# PIC32ETH_Pic.net
KiCad netlist of a schematic drawn in Altium Designer
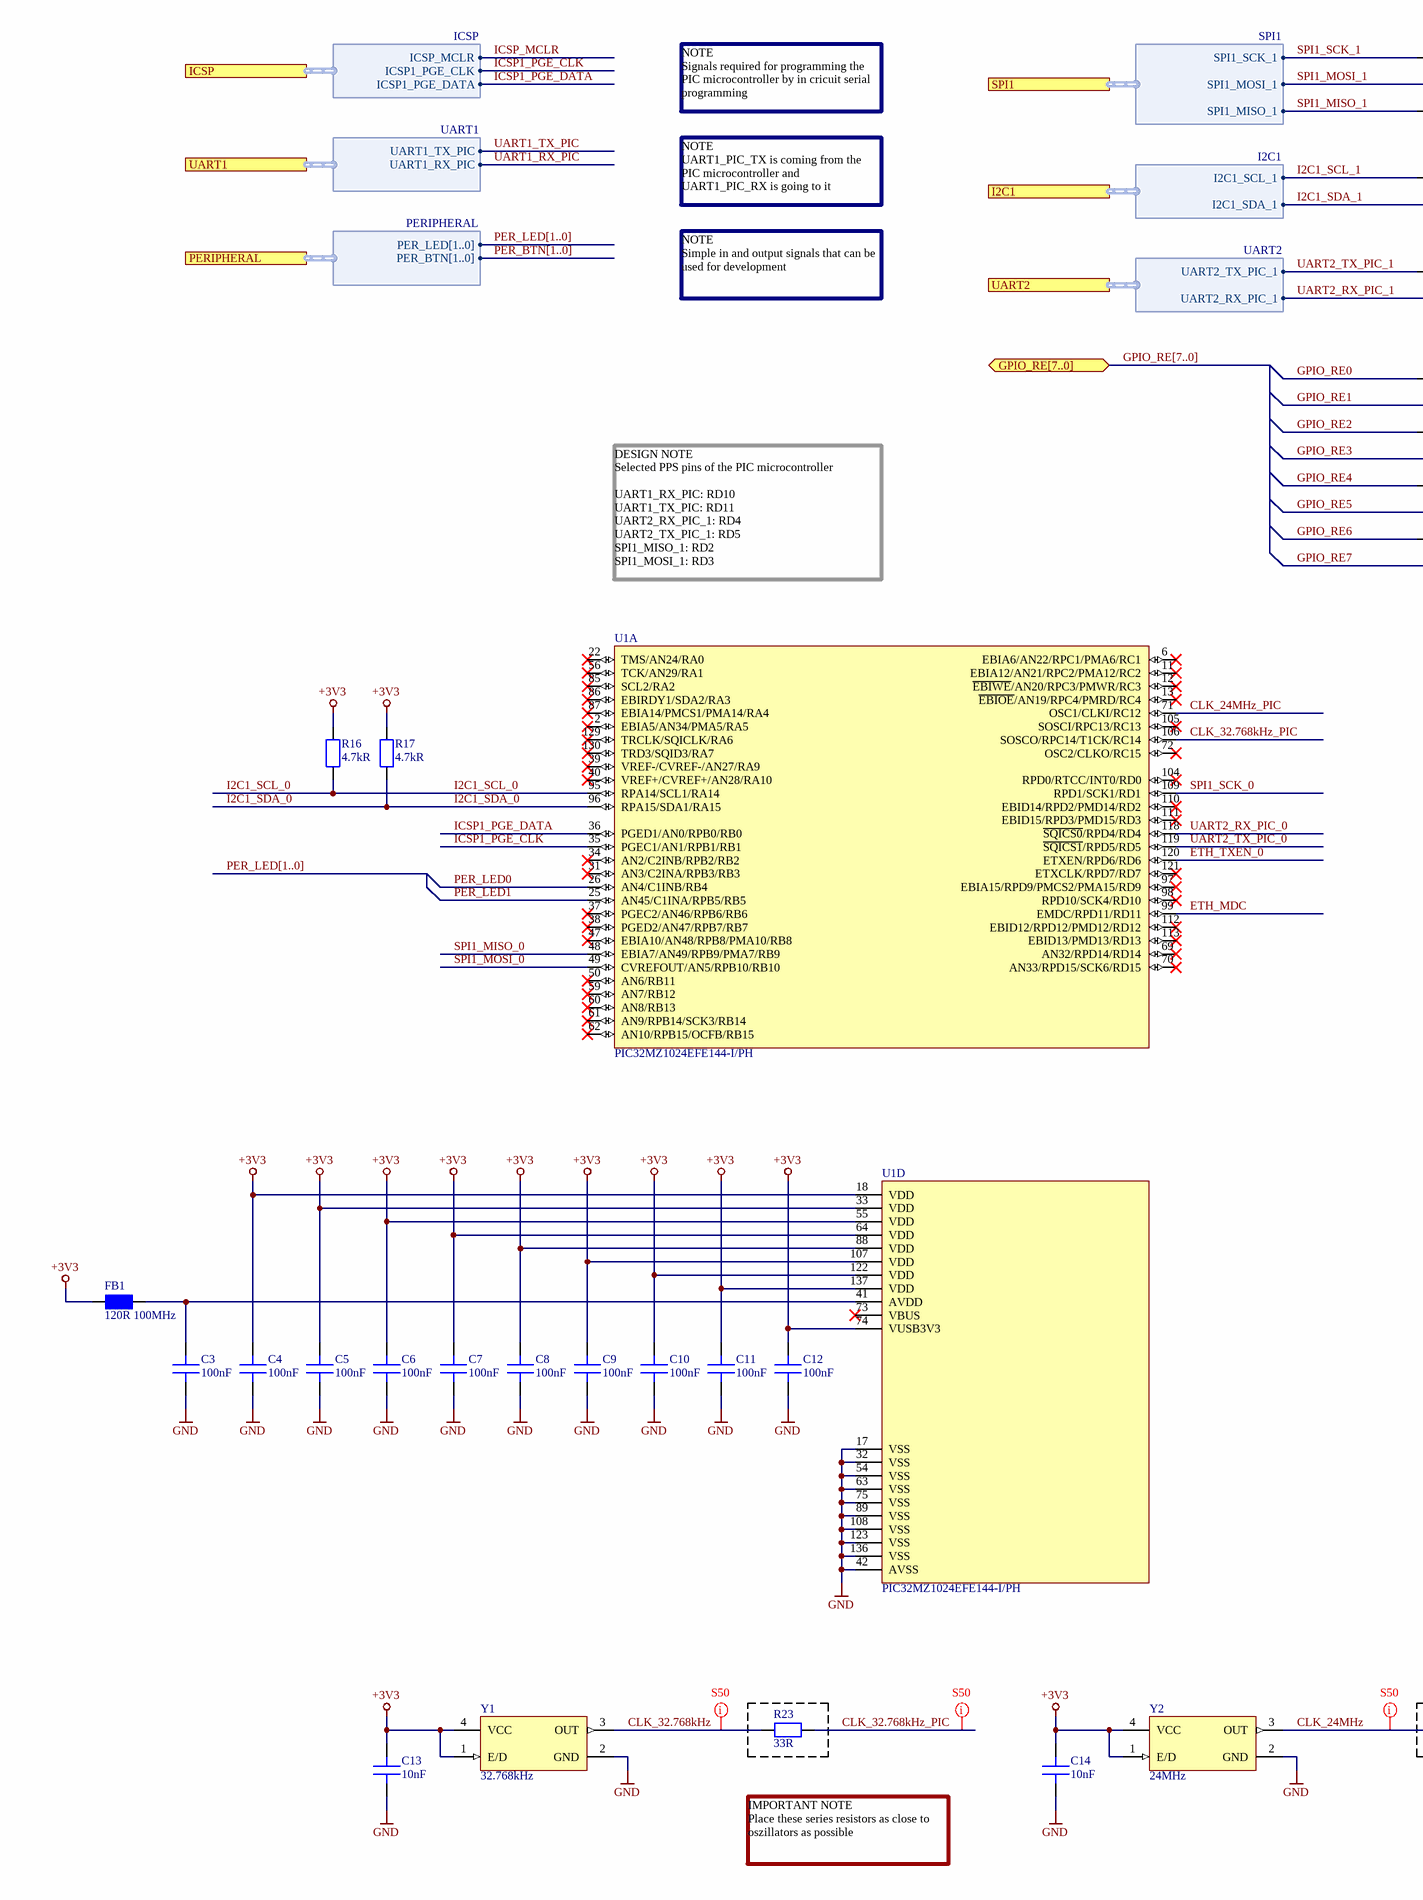
[diagram p0: PIC32ETH_Pic.SchDoc, left]
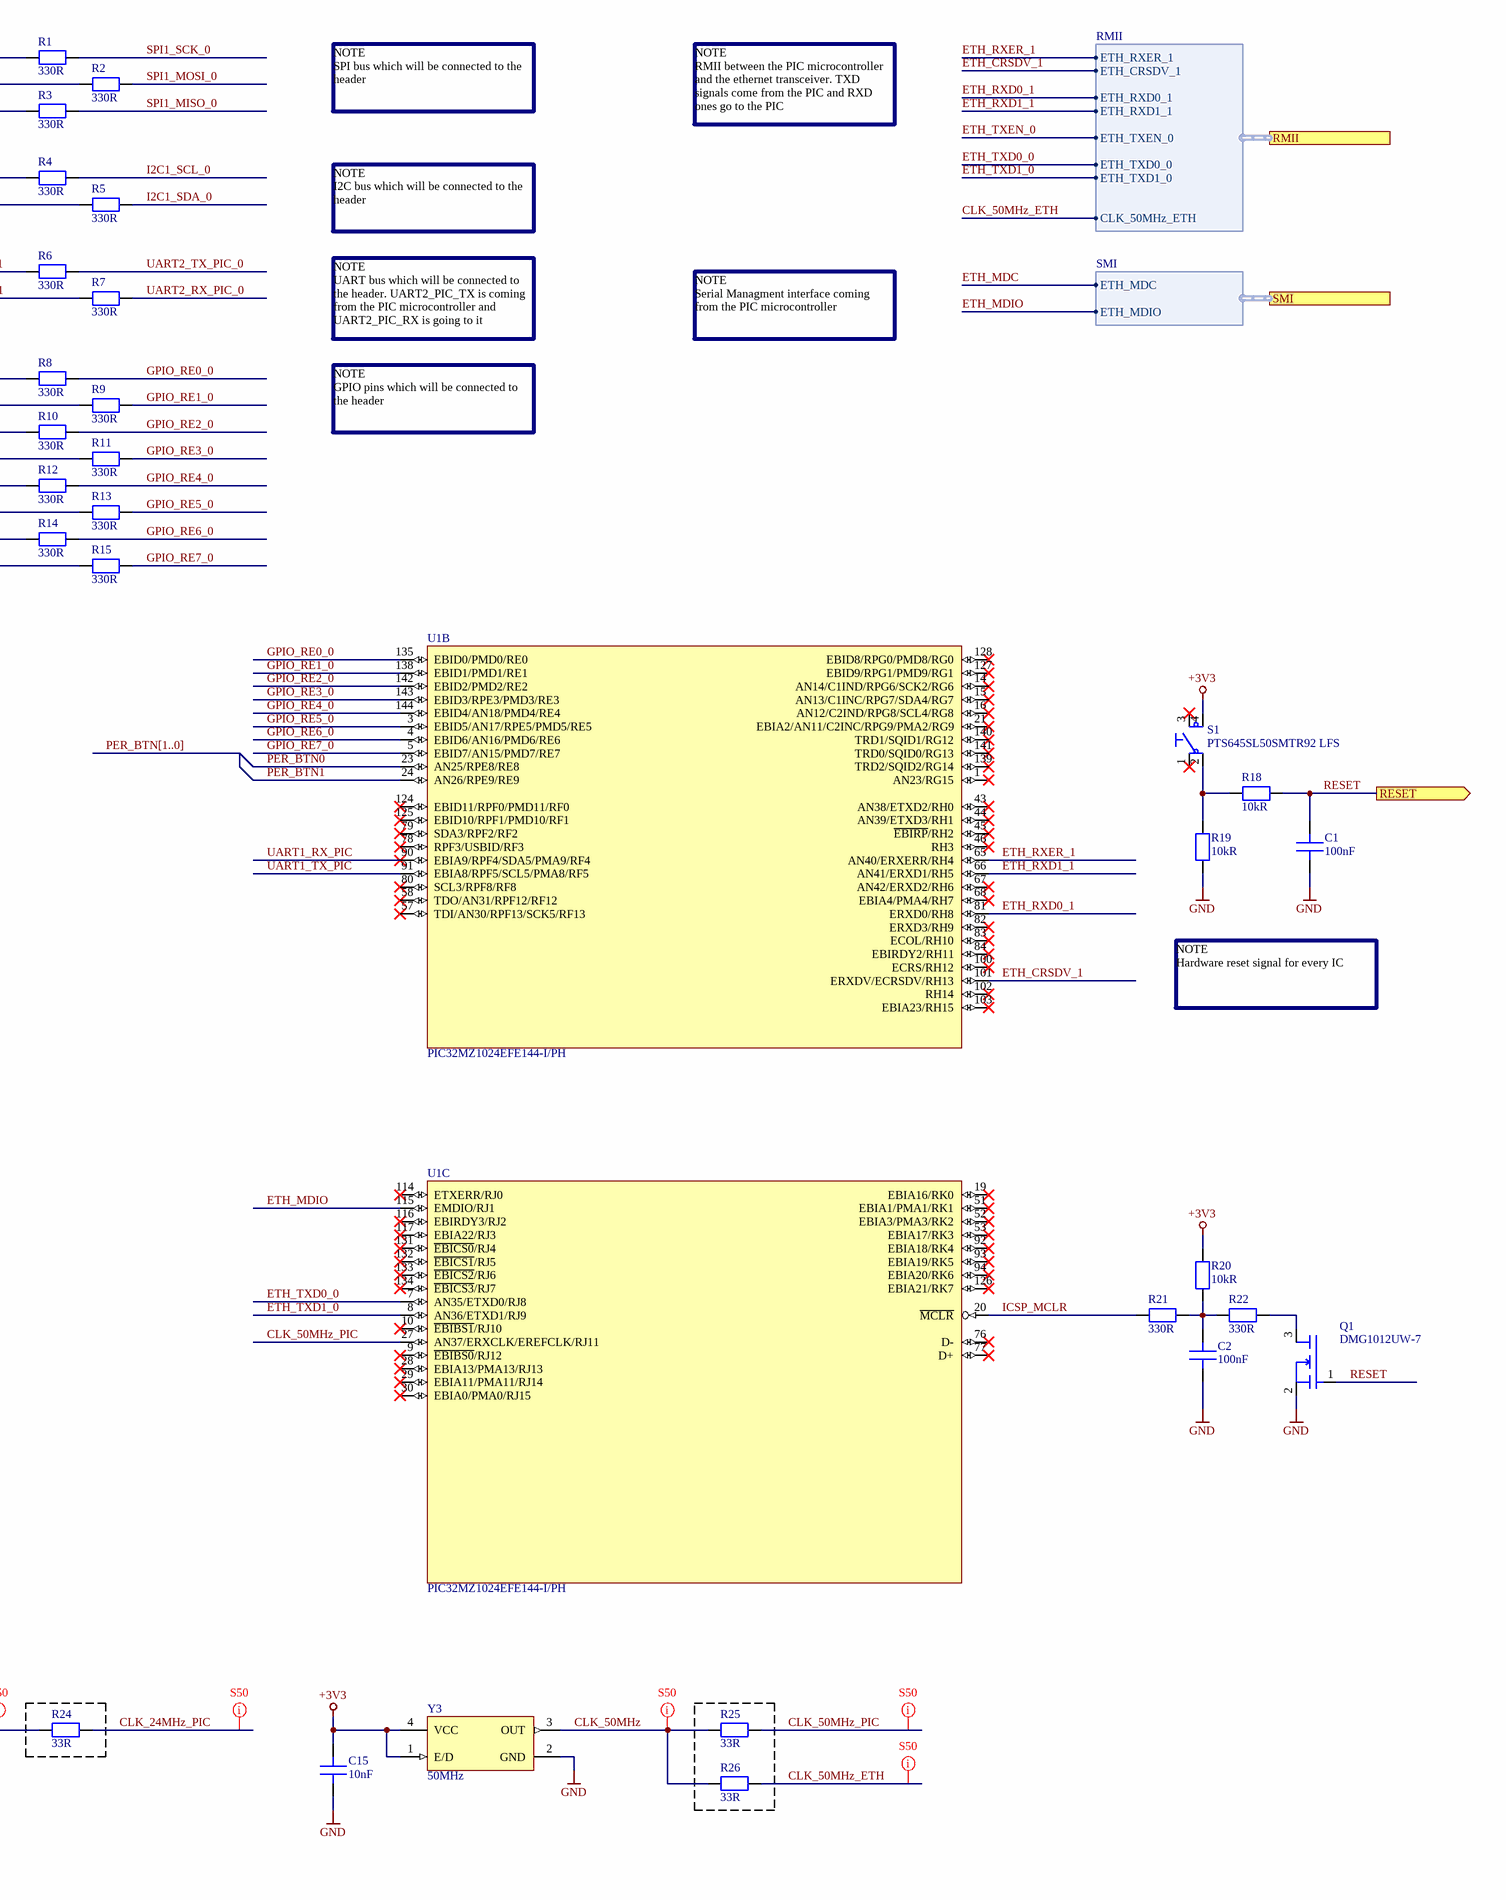
[diagram p1: PIC32ETH_Pic.SchDoc, right]

(export (version "E")
  (design (tool "Eeschema 10.0.6"))
  (components
    (comp (ref "C1")
      (value "100nF")
      (footprint "C_CHIP2012N")
      (description "C CERAMIC 100nF 50V 10% 2012")
      (fields (field (name "MANUFACTURER") "Kemet") (field (name "PART NUMBER") "C0805C104K5RACTU"))
      (libsource (lib "PIC32ETH") (part "C_C0805C104K5RACTU"))
    )
    (comp (ref "C2")
      (value "100nF")
      (footprint "C_CHIP2012N")
      (description "C CERAMIC 100nF 50V 10% 2012")
      (fields (field (name "MANUFACTURER") "Kemet") (field (name "PART NUMBER") "C0805C104K5RACTU"))
      (libsource (lib "PIC32ETH") (part "C_C0805C104K5RACTU"))
    )
    (comp (ref "C3")
      (value "100nF")
      (footprint "C_CHIP2012N")
      (description "C CERAMIC 100nF 50V 10% 2012")
      (fields (field (name "MANUFACTURER") "Kemet") (field (name "PART NUMBER") "C0805C104K5RACTU"))
      (libsource (lib "PIC32ETH") (part "C_C0805C104K5RACTU"))
    )
    (comp (ref "C4")
      (value "100nF")
      (footprint "C_CHIP2012N")
      (description "C CERAMIC 100nF 50V 10% 2012")
      (fields (field (name "MANUFACTURER") "Kemet") (field (name "PART NUMBER") "C0805C104K5RACTU"))
      (libsource (lib "PIC32ETH") (part "C_C0805C104K5RACTU"))
    )
    (comp (ref "C5")
      (value "100nF")
      (footprint "C_CHIP2012N")
      (description "C CERAMIC 100nF 50V 10% 2012")
      (fields (field (name "MANUFACTURER") "Kemet") (field (name "PART NUMBER") "C0805C104K5RACTU"))
      (libsource (lib "PIC32ETH") (part "C_C0805C104K5RACTU"))
    )
    (comp (ref "C6")
      (value "100nF")
      (footprint "C_CHIP2012N")
      (description "C CERAMIC 100nF 50V 10% 2012")
      (fields (field (name "MANUFACTURER") "Kemet") (field (name "PART NUMBER") "C0805C104K5RACTU"))
      (libsource (lib "PIC32ETH") (part "C_C0805C104K5RACTU"))
    )
    (comp (ref "C7")
      (value "100nF")
      (footprint "C_CHIP2012N")
      (description "C CERAMIC 100nF 50V 10% 2012")
      (fields (field (name "MANUFACTURER") "Kemet") (field (name "PART NUMBER") "C0805C104K5RACTU"))
      (libsource (lib "PIC32ETH") (part "C_C0805C104K5RACTU"))
    )
    (comp (ref "C8")
      (value "100nF")
      (footprint "C_CHIP2012N")
      (description "C CERAMIC 100nF 50V 10% 2012")
      (fields (field (name "MANUFACTURER") "Kemet") (field (name "PART NUMBER") "C0805C104K5RACTU"))
      (libsource (lib "PIC32ETH") (part "C_C0805C104K5RACTU"))
    )
    (comp (ref "C9")
      (value "100nF")
      (footprint "C_CHIP2012N")
      (description "C CERAMIC 100nF 50V 10% 2012")
      (fields (field (name "MANUFACTURER") "Kemet") (field (name "PART NUMBER") "C0805C104K5RACTU"))
      (libsource (lib "PIC32ETH") (part "C_C0805C104K5RACTU"))
    )
    (comp (ref "C10")
      (value "100nF")
      (footprint "C_CHIP2012N")
      (description "C CERAMIC 100nF 50V 10% 2012")
      (fields (field (name "MANUFACTURER") "Kemet") (field (name "PART NUMBER") "C0805C104K5RACTU"))
      (libsource (lib "PIC32ETH") (part "C_C0805C104K5RACTU"))
    )
    (comp (ref "C11")
      (value "100nF")
      (footprint "C_CHIP2012N")
      (description "C CERAMIC 100nF 50V 10% 2012")
      (fields (field (name "MANUFACTURER") "Kemet") (field (name "PART NUMBER") "C0805C104K5RACTU"))
      (libsource (lib "PIC32ETH") (part "C_C0805C104K5RACTU"))
    )
    (comp (ref "C12")
      (value "100nF")
      (footprint "C_CHIP2012N")
      (description "C CERAMIC 100nF 50V 10% 2012")
      (fields (field (name "MANUFACTURER") "Kemet") (field (name "PART NUMBER") "C0805C104K5RACTU"))
      (libsource (lib "PIC32ETH") (part "C_C0805C104K5RACTU"))
    )
    (comp (ref "C13")
      (value "10nF")
      (footprint "C_CHIP2012N")
      (description "C CERAMIC 10nF 50V 10% 2012")
      (fields (field (name "MANUFACTURER") "Kemet") (field (name "PART NUMBER") "C0805C103K5RACTU"))
      (libsource (lib "PIC32ETH") (part "C_C0805C103K5RACTU"))
    )
    (comp (ref "C14")
      (value "10nF")
      (footprint "C_CHIP2012N")
      (description "C CERAMIC 10nF 50V 10% 2012")
      (fields (field (name "MANUFACTURER") "Kemet") (field (name "PART NUMBER") "C0805C103K5RACTU"))
      (libsource (lib "PIC32ETH") (part "C_C0805C103K5RACTU"))
    )
    (comp (ref "C15")
      (value "10nF")
      (footprint "C_CHIP2012N")
      (description "C CERAMIC 10nF 50V 10% 2012")
      (fields (field (name "MANUFACTURER") "Kemet") (field (name "PART NUMBER") "C0805C103K5RACTU"))
      (libsource (lib "PIC32ETH") (part "C_C0805C103K5RACTU"))
    )
    (comp (ref "FB1")
      (value "120R 100MHz")
      (footprint "FB_CHIP3216N")
      (description "FB 120R 100MHz 6A 3216")
      (fields
        (field (name "MANUFACTURER") "Murata Electronics")
        (field (name "PART NUMBER") "BLM31KN121SN1L")
      )
      (libsource (lib "PIC32ETH") (part "FB_BLM31KN121SN1L"))
    )
    (comp (ref "Q1")
      (value "DMG1012UW-7")
      (footprint "Q_SOT65P210X100-3N")
      (description "Q MOSFET N-CH 20V 1A SOT-323")
      (fields (field (name "MANUFACTURER") "Diodes Incorporated") (field (name "POWER") "290mW"))
      (libsource (lib "PIC32ETH") (part "Q_DMG1012UW-7"))
    )
    (comp (ref "R1")
      (value "330R")
      (footprint "R_CHIP2012N")
      (description "R SMT 330R 1% 125mW 2012")
      (fields
        (field (name "MANUFACTURER") "Stackpole Electronics Inc")
        (field (name "PART NUMBER") "RMCF0805FT330R")
      )
      (libsource (lib "PIC32ETH") (part "R_RMCF0805FT330R"))
    )
    (comp (ref "R2")
      (value "330R")
      (footprint "R_CHIP2012N")
      (description "R SMT 330R 1% 125mW 2012")
      (fields
        (field (name "MANUFACTURER") "Stackpole Electronics Inc")
        (field (name "PART NUMBER") "RMCF0805FT330R")
      )
      (libsource (lib "PIC32ETH") (part "R_RMCF0805FT330R"))
    )
    (comp (ref "R3")
      (value "330R")
      (footprint "R_CHIP2012N")
      (description "R SMT 330R 1% 125mW 2012")
      (fields
        (field (name "MANUFACTURER") "Stackpole Electronics Inc")
        (field (name "PART NUMBER") "RMCF0805FT330R")
      )
      (libsource (lib "PIC32ETH") (part "R_RMCF0805FT330R"))
    )
    (comp (ref "R4")
      (value "330R")
      (footprint "R_CHIP2012N")
      (description "R SMT 330R 1% 125mW 2012")
      (fields
        (field (name "MANUFACTURER") "Stackpole Electronics Inc")
        (field (name "PART NUMBER") "RMCF0805FT330R")
      )
      (libsource (lib "PIC32ETH") (part "R_RMCF0805FT330R"))
    )
    (comp (ref "R5")
      (value "330R")
      (footprint "R_CHIP2012N")
      (description "R SMT 330R 1% 125mW 2012")
      (fields
        (field (name "MANUFACTURER") "Stackpole Electronics Inc")
        (field (name "PART NUMBER") "RMCF0805FT330R")
      )
      (libsource (lib "PIC32ETH") (part "R_RMCF0805FT330R"))
    )
    (comp (ref "R6")
      (value "330R")
      (footprint "R_CHIP2012N")
      (description "R SMT 330R 1% 125mW 2012")
      (fields
        (field (name "MANUFACTURER") "Stackpole Electronics Inc")
        (field (name "PART NUMBER") "RMCF0805FT330R")
      )
      (libsource (lib "PIC32ETH") (part "R_RMCF0805FT330R"))
    )
    (comp (ref "R7")
      (value "330R")
      (footprint "R_CHIP2012N")
      (description "R SMT 330R 1% 125mW 2012")
      (fields
        (field (name "MANUFACTURER") "Stackpole Electronics Inc")
        (field (name "PART NUMBER") "RMCF0805FT330R")
      )
      (libsource (lib "PIC32ETH") (part "R_RMCF0805FT330R"))
    )
    (comp (ref "R8")
      (value "330R")
      (footprint "R_CHIP2012N")
      (description "R SMT 330R 1% 125mW 2012")
      (fields
        (field (name "MANUFACTURER") "Stackpole Electronics Inc")
        (field (name "PART NUMBER") "RMCF0805FT330R")
      )
      (libsource (lib "PIC32ETH") (part "R_RMCF0805FT330R"))
    )
    (comp (ref "R9")
      (value "330R")
      (footprint "R_CHIP2012N")
      (description "R SMT 330R 1% 125mW 2012")
      (fields
        (field (name "MANUFACTURER") "Stackpole Electronics Inc")
        (field (name "PART NUMBER") "RMCF0805FT330R")
      )
      (libsource (lib "PIC32ETH") (part "R_RMCF0805FT330R"))
    )
    (comp (ref "R10")
      (value "330R")
      (footprint "R_CHIP2012N")
      (description "R SMT 330R 1% 125mW 2012")
      (fields
        (field (name "MANUFACTURER") "Stackpole Electronics Inc")
        (field (name "PART NUMBER") "RMCF0805FT330R")
      )
      (libsource (lib "PIC32ETH") (part "R_RMCF0805FT330R"))
    )
    (comp (ref "R11")
      (value "330R")
      (footprint "R_CHIP2012N")
      (description "R SMT 330R 1% 125mW 2012")
      (fields
        (field (name "MANUFACTURER") "Stackpole Electronics Inc")
        (field (name "PART NUMBER") "RMCF0805FT330R")
      )
      (libsource (lib "PIC32ETH") (part "R_RMCF0805FT330R"))
    )
    (comp (ref "R12")
      (value "330R")
      (footprint "R_CHIP2012N")
      (description "R SMT 330R 1% 125mW 2012")
      (fields
        (field (name "MANUFACTURER") "Stackpole Electronics Inc")
        (field (name "PART NUMBER") "RMCF0805FT330R")
      )
      (libsource (lib "PIC32ETH") (part "R_RMCF0805FT330R"))
    )
    (comp (ref "R13")
      (value "330R")
      (footprint "R_CHIP2012N")
      (description "R SMT 330R 1% 125mW 2012")
      (fields
        (field (name "MANUFACTURER") "Stackpole Electronics Inc")
        (field (name "PART NUMBER") "RMCF0805FT330R")
      )
      (libsource (lib "PIC32ETH") (part "R_RMCF0805FT330R"))
    )
    (comp (ref "R14")
      (value "330R")
      (footprint "R_CHIP2012N")
      (description "R SMT 330R 1% 125mW 2012")
      (fields
        (field (name "MANUFACTURER") "Stackpole Electronics Inc")
        (field (name "PART NUMBER") "RMCF0805FT330R")
      )
      (libsource (lib "PIC32ETH") (part "R_RMCF0805FT330R"))
    )
    (comp (ref "R15")
      (value "330R")
      (footprint "R_CHIP2012N")
      (description "R SMT 330R 1% 125mW 2012")
      (fields
        (field (name "MANUFACTURER") "Stackpole Electronics Inc")
        (field (name "PART NUMBER") "RMCF0805FT330R")
      )
      (libsource (lib "PIC32ETH") (part "R_RMCF0805FT330R"))
    )
    (comp (ref "R16")
      (value "4.7kR")
      (footprint "R_CHIP2012N")
      (description "R SMT 4.7kR 1% 125mW 2012")
      (fields
        (field (name "MANUFACTURER") "Stackpole Electronics Inc")
        (field (name "PART NUMBER") "RMCF0805FT4K70")
      )
      (libsource (lib "PIC32ETH") (part "R_RMCF0805FT4K70"))
    )
    (comp (ref "R17")
      (value "4.7kR")
      (footprint "R_CHIP2012N")
      (description "R SMT 4.7kR 1% 125mW 2012")
      (fields
        (field (name "MANUFACTURER") "Stackpole Electronics Inc")
        (field (name "PART NUMBER") "RMCF0805FT4K70")
      )
      (libsource (lib "PIC32ETH") (part "R_RMCF0805FT4K70"))
    )
    (comp (ref "R18")
      (value "10kR")
      (footprint "R_CHIP2012N")
      (description "R SMT 10kR 1% 125mW 2012")
      (fields
        (field (name "MANUFACTURER") "Stackpole Electronics Inc")
        (field (name "PART NUMBER") "RMCF0805FT10K0")
      )
      (libsource (lib "PIC32ETH") (part "R_RMCF0805FT10K0"))
    )
    (comp (ref "R19")
      (value "10kR")
      (footprint "R_CHIP2012N")
      (description "R SMT 10kR 1% 125mW 2012")
      (fields
        (field (name "MANUFACTURER") "Stackpole Electronics Inc")
        (field (name "PART NUMBER") "RMCF0805FT10K0")
      )
      (libsource (lib "PIC32ETH") (part "R_RMCF0805FT10K0"))
    )
    (comp (ref "R20")
      (value "10kR")
      (footprint "R_CHIP2012N")
      (description "R SMT 10kR 1% 125mW 2012")
      (fields
        (field (name "MANUFACTURER") "Stackpole Electronics Inc")
        (field (name "PART NUMBER") "RMCF0805FT10K0")
      )
      (libsource (lib "PIC32ETH") (part "R_RMCF0805FT10K0"))
    )
    (comp (ref "R21")
      (value "330R")
      (footprint "R_CHIP2012N")
      (description "R SMT 330R 1% 125mW 2012")
      (fields
        (field (name "MANUFACTURER") "Stackpole Electronics Inc")
        (field (name "PART NUMBER") "RMCF0805FT330R")
      )
      (libsource (lib "PIC32ETH") (part "R_RMCF0805FT330R"))
    )
    (comp (ref "R22")
      (value "330R")
      (footprint "R_CHIP2012N")
      (description "R SMT 330R 1% 125mW 2012")
      (fields
        (field (name "MANUFACTURER") "Stackpole Electronics Inc")
        (field (name "PART NUMBER") "RMCF0805FT330R")
      )
      (libsource (lib "PIC32ETH") (part "R_RMCF0805FT330R"))
    )
    (comp (ref "R23")
      (value "33R")
      (footprint "R_CHIP2012N")
      (description "R SMT 33R 1% 125mW 2012")
      (fields
        (field (name "MANUFACTURER") "Stackpole Electronics Inc")
        (field (name "PART NUMBER") "RMCF0805FT33R0")
      )
      (libsource (lib "PIC32ETH") (part "R_RMCF0805FT33R0"))
    )
    (comp (ref "R24")
      (value "33R")
      (footprint "R_CHIP2012N")
      (description "R SMT 33R 1% 125mW 2012")
      (fields
        (field (name "MANUFACTURER") "Stackpole Electronics Inc")
        (field (name "PART NUMBER") "RMCF0805FT33R0")
      )
      (libsource (lib "PIC32ETH") (part "R_RMCF0805FT33R0"))
    )
    (comp (ref "R25")
      (value "33R")
      (footprint "R_CHIP2012N")
      (description "R SMT 33R 1% 125mW 2012")
      (fields
        (field (name "MANUFACTURER") "Stackpole Electronics Inc")
        (field (name "PART NUMBER") "RMCF0805FT33R0")
      )
      (libsource (lib "PIC32ETH") (part "R_RMCF0805FT33R0"))
    )
    (comp (ref "R26")
      (value "33R")
      (footprint "R_CHIP2012N")
      (description "R SMT 33R 1% 125mW 2012")
      (fields
        (field (name "MANUFACTURER") "Stackpole Electronics Inc")
        (field (name "PART NUMBER") "RMCF0805FT33R0")
      )
      (libsource (lib "PIC32ETH") (part "R_RMCF0805FT33R0"))
    )
    (comp (ref "S1")
      (value "PTS645SL50SMTR92 LFS")
      (footprint "S_CHIPP620X620-4N")
      (description "S TACTILE SPST-NO 12V 50mA SMT")
      (fields (field (name "MANUFACTURER") "C&K") (field (name "VOLTAGE") "12V"))
      (libsource (lib "PIC32ETH") (part "S_PTS645SL50SMTR92LFS"))
    )
    (comp (ref "U1")
      (value "PIC32MZ1024EFE144-I/PH")
      (footprint "U_QFP40P1800X1800X120-144N")
      (description "U MCU 32BIT 1MB 144-TQFP")
      (fields (field (name "MANUFACTURER") "Microchip Technology"))
      (libsource (lib "PIC32ETH") (part "U_PIC32MZ1024EFE144-I/PH"))
    )
    (comp (ref "Y1")
      (value "32.768kHz")
      (footprint "Y_CHIPP320X250-4N")
      (description "Y OSCILLATOR 32.768kHz CMOS SMT")
      (fields (field (name "MANUFACTURER") "ECS Inc.") (field (name "PART NUMBER") "ECS-327ATQMV-AS-TR"))
      (libsource (lib "PIC32ETH") (part "Y_ECS-327ATQMV-AS-TR"))
    )
    (comp (ref "Y2")
      (value "24MHz")
      (footprint "Y_CHIPP320X250-4N")
      (description "Y OSCILLATOR 24MHz HCMOS SMT")
      (fields (field (name "MANUFACTURER") "ECS Inc.") (field (name "PART NUMBER") "ECS-3225MV-240-CN-TR"))
      (libsource (lib "PIC32ETH") (part "Y_ECS-3225MV-240-CN-TR"))
    )
    (comp (ref "Y3")
      (value "50MHz")
      (footprint "Y_CHIPP320X250-4N")
      (description "Y OSCILLATOR 50MHz HCMOS SMT")
      (fields (field (name "MANUFACTURER") "ECS Inc.") (field (name "PART NUMBER") "ECS-3225MV-500-BN-TR"))
      (libsource (lib "PIC32ETH") (part "Y_ECS-3225MV-500-BN-TR"))
    )
  )
  (nets
    (net (code "9") (name "+3V3") (class "Default")
      (node (ref "C10") (pin "1") (pinfunction "1_1") (pintype "passive"))
      (node (ref "C11") (pin "1") (pinfunction "1_1") (pintype "passive"))
      (node (ref "C12") (pin "1") (pinfunction "1_1") (pintype "passive"))
      (node (ref "C13") (pin "2") (pinfunction "2_2") (pintype "passive"))
      (node (ref "C14") (pin "2") (pinfunction "2_2") (pintype "passive"))
      (node (ref "C15") (pin "2") (pinfunction "2_2") (pintype "passive"))
      (node (ref "C4") (pin "1") (pinfunction "1_1") (pintype "passive"))
      (node (ref "C5") (pin "1") (pinfunction "1_1") (pintype "passive"))
      (node (ref "C6") (pin "1") (pinfunction "1_1") (pintype "passive"))
      (node (ref "C7") (pin "1") (pinfunction "1_1") (pintype "passive"))
      (node (ref "C8") (pin "1") (pinfunction "1_1") (pintype "passive"))
      (node (ref "C9") (pin "1") (pinfunction "1_1") (pintype "passive"))
      (node (ref "FB1") (pin "1") (pinfunction "1_1") (pintype "passive"))
      (node (ref "R16") (pin "2") (pinfunction "2_2") (pintype "passive"))
      (node (ref "R17") (pin "2") (pinfunction "2_2") (pintype "passive"))
      (node (ref "R20") (pin "2") (pinfunction "2_2") (pintype "passive"))
      (node (ref "S1") (pin "4") (pinfunction "4_4") (pintype "passive"))
      (node (ref "U1") (pin "107") (pinfunction "VDD_107") (pintype "power_in"))
      (node (ref "U1") (pin "122") (pinfunction "VDD_122") (pintype "power_in"))
      (node (ref "U1") (pin "137") (pinfunction "VDD_137") (pintype "power_in"))
      (node (ref "U1") (pin "18") (pinfunction "VDD_18") (pintype "power_in"))
      (node (ref "U1") (pin "33") (pinfunction "VDD_33") (pintype "power_in"))
      (node (ref "U1") (pin "55") (pinfunction "VDD_55") (pintype "power_in"))
      (node (ref "U1") (pin "64") (pinfunction "VDD_64") (pintype "power_in"))
      (node (ref "U1") (pin "74") (pinfunction "VUSB3V3_74") (pintype "power_in"))
      (node (ref "U1") (pin "88") (pinfunction "VDD_88") (pintype "power_in"))
      (node (ref "Y1") (pin "1") (pinfunction "E/D_1") (pintype "input"))
      (node (ref "Y1") (pin "4") (pinfunction "VCC_4") (pintype "power_in"))
      (node (ref "Y2") (pin "1") (pinfunction "E/D_1") (pintype "input"))
      (node (ref "Y2") (pin "4") (pinfunction "VCC_4") (pintype "power_in"))
      (node (ref "Y3") (pin "1") (pinfunction "E/D_1") (pintype "input"))
      (node (ref "Y3") (pin "4") (pinfunction "VCC_4") (pintype "power_in"))
    )
    (net (code "10") (name "/CLK_24MHz") (class "Default")
      (node (ref "R24") (pin "1") (pinfunction "1_1") (pintype "passive"))
      (node (ref "Y2") (pin "3") (pinfunction "OUT_3") (pintype "output"))
    )
    (net (code "11") (name "/CLK_24MHz_PIC") (class "Default")
      (node (ref "R24") (pin "2") (pinfunction "2_2") (pintype "passive"))
      (node (ref "U1") (pin "71") (pinfunction "OSC1/CLKI/RC12_71") (pintype "bidirectional"))
    )
    (net (code "12") (name "/CLK_32.768kHz") (class "Default")
      (node (ref "R23") (pin "1") (pinfunction "1_1") (pintype "passive"))
      (node (ref "Y1") (pin "3") (pinfunction "OUT_3") (pintype "output"))
    )
    (net (code "13") (name "/CLK_32.768kHz_PIC") (class "Default")
      (node (ref "R23") (pin "2") (pinfunction "2_2") (pintype "passive"))
      (node (ref "U1") (pin "106") (pinfunction "SOSCO/RPC14/T1CK/RC14_106") (pintype "bidirectional"))
    )
    (net (code "14") (name "/CLK_50MHz") (class "Default")
      (node (ref "R25") (pin "1") (pinfunction "1_1") (pintype "passive"))
      (node (ref "R26") (pin "1") (pinfunction "1_1") (pintype "passive"))
      (node (ref "Y3") (pin "3") (pinfunction "OUT_3") (pintype "output"))
    )
    (net (code "15") (name "/CLK_50MHz_ETH") (class "Default")
      (node (ref "R26") (pin "2") (pinfunction "2_2") (pintype "passive"))
    )
    (net (code "16") (name "/CLK_50MHz_PIC") (class "Default")
      (node (ref "R25") (pin "2") (pinfunction "2_2") (pintype "passive"))
      (node (ref "U1") (pin "27") (pinfunction "AN37/ERXCLK/EREFCLK/RJ11_27") (pintype "bidirectional"))
    )
    (net (code "17") (name "/ETH_CRSDV_1") (class "Default")
      (node (ref "U1") (pin "101") (pinfunction "ERXDV/ECRSDV/RH13_101") (pintype "bidirectional"))
    )
    (net (code "18") (name "/ETH_MDC") (class "Default")
      (node (ref "U1") (pin "99") (pinfunction "EMDC/RPD11/RD11_99") (pintype "bidirectional"))
    )
    (net (code "19") (name "/ETH_MDIO") (class "Default")
      (node (ref "U1") (pin "115") (pinfunction "EMDIO/RJ1_115") (pintype "bidirectional"))
    )
    (net (code "20") (name "/ETH_RXD0_1") (class "Default")
      (node (ref "U1") (pin "81") (pinfunction "ERXD0/RH8_81") (pintype "bidirectional"))
    )
    (net (code "21") (name "/ETH_RXD1_1") (class "Default")
      (node (ref "U1") (pin "66") (pinfunction "AN41/ERXD1/RH5_66") (pintype "bidirectional"))
    )
    (net (code "22") (name "/ETH_RXER_1") (class "Default")
      (node (ref "U1") (pin "65") (pinfunction "AN40/ERXERR/RH4_65") (pintype "bidirectional"))
    )
    (net (code "23") (name "/ETH_TXD0_0") (class "Default")
      (node (ref "U1") (pin "7") (pinfunction "AN35/ETXD0/RJ8_7") (pintype "bidirectional"))
    )
    (net (code "24") (name "/ETH_TXD1_0") (class "Default")
      (node (ref "U1") (pin "8") (pinfunction "AN36/ETXD1/RJ9_8") (pintype "bidirectional"))
    )
    (net (code "25") (name "/ETH_TXEN_0") (class "Default")
      (node (ref "U1") (pin "120") (pinfunction "ETXEN/RPD6/RD6_120") (pintype "bidirectional"))
    )
    (net (code "26") (name "/GPIO_RE0") (class "Default")
      (node (ref "R8") (pin "1") (pinfunction "1_1") (pintype "passive"))
    )
    (net (code "27") (name "/GPIO_RE0_0") (class "Default")
      (node (ref "R8") (pin "2") (pinfunction "2_2") (pintype "passive"))
      (node (ref "U1") (pin "135") (pinfunction "EBID0/PMD0/RE0_135") (pintype "bidirectional"))
    )
    (net (code "28") (name "/GPIO_RE1") (class "Default")
      (node (ref "R9") (pin "1") (pinfunction "1_1") (pintype "passive"))
    )
    (net (code "29") (name "/GPIO_RE1_0") (class "Default")
      (node (ref "R9") (pin "2") (pinfunction "2_2") (pintype "passive"))
      (node (ref "U1") (pin "138") (pinfunction "EBID1/PMD1/RE1_138") (pintype "bidirectional"))
    )
    (net (code "30") (name "/GPIO_RE2") (class "Default")
      (node (ref "R10") (pin "1") (pinfunction "1_1") (pintype "passive"))
    )
    (net (code "31") (name "/GPIO_RE2_0") (class "Default")
      (node (ref "R10") (pin "2") (pinfunction "2_2") (pintype "passive"))
      (node (ref "U1") (pin "142") (pinfunction "EBID2/PMD2/RE2_142") (pintype "bidirectional"))
    )
    (net (code "32") (name "/GPIO_RE3") (class "Default")
      (node (ref "R11") (pin "1") (pinfunction "1_1") (pintype "passive"))
    )
    (net (code "33") (name "/GPIO_RE3_0") (class "Default")
      (node (ref "R11") (pin "2") (pinfunction "2_2") (pintype "passive"))
      (node (ref "U1") (pin "143") (pinfunction "EBID3/RPE3/PMD3/RE3_143") (pintype "bidirectional"))
    )
    (net (code "34") (name "/GPIO_RE4") (class "Default")
      (node (ref "R12") (pin "1") (pinfunction "1_1") (pintype "passive"))
    )
    (net (code "35") (name "/GPIO_RE4_0") (class "Default")
      (node (ref "R12") (pin "2") (pinfunction "2_2") (pintype "passive"))
      (node (ref "U1") (pin "144") (pinfunction "EBID4/AN18/PMD4/RE4_144") (pintype "bidirectional"))
    )
    (net (code "36") (name "/GPIO_RE5") (class "Default")
      (node (ref "R13") (pin "1") (pinfunction "1_1") (pintype "passive"))
    )
    (net (code "37") (name "/GPIO_RE5_0") (class "Default")
      (node (ref "R13") (pin "2") (pinfunction "2_2") (pintype "passive"))
      (node (ref "U1") (pin "3") (pinfunction "EBID5/AN17/RPE5/PMD5/RE5_3") (pintype "bidirectional"))
    )
    (net (code "38") (name "/GPIO_RE6") (class "Default")
      (node (ref "R14") (pin "1") (pinfunction "1_1") (pintype "passive"))
    )
    (net (code "39") (name "/GPIO_RE6_0") (class "Default")
      (node (ref "R14") (pin "2") (pinfunction "2_2") (pintype "passive"))
      (node (ref "U1") (pin "4") (pinfunction "EBID6/AN16/PMD6/RE6_4") (pintype "bidirectional"))
    )
    (net (code "40") (name "/GPIO_RE7") (class "Default")
      (node (ref "R15") (pin "1") (pinfunction "1_1") (pintype "passive"))
    )
    (net (code "41") (name "/GPIO_RE7_0") (class "Default")
      (node (ref "R15") (pin "2") (pinfunction "2_2") (pintype "passive"))
      (node (ref "U1") (pin "5") (pinfunction "EBID7/AN15/PMD7/RE7_5") (pintype "bidirectional"))
    )
    (net (code "43") (name "/I2C1_SCL_0") (class "Default")
      (node (ref "R16") (pin "1") (pinfunction "1_1") (pintype "passive"))
      (node (ref "R4") (pin "2") (pinfunction "2_2") (pintype "passive"))
      (node (ref "U1") (pin "95") (pinfunction "RPA14/SCL1/RA14_95") (pintype "bidirectional"))
    )
    (net (code "44") (name "/I2C1_SCL_1") (class "Default")
      (node (ref "R4") (pin "1") (pinfunction "1_1") (pintype "passive"))
    )
    (net (code "45") (name "/I2C1_SDA_0") (class "Default")
      (node (ref "R17") (pin "1") (pinfunction "1_1") (pintype "passive"))
      (node (ref "R5") (pin "2") (pinfunction "2_2") (pintype "passive"))
      (node (ref "U1") (pin "96") (pinfunction "RPA15/SDA1/RA15_96") (pintype "bidirectional"))
    )
    (net (code "46") (name "/I2C1_SDA_1") (class "Default")
      (node (ref "R5") (pin "1") (pinfunction "1_1") (pintype "passive"))
    )
    (net (code "47") (name "/ICSP1_PGE_CLK") (class "Default")
      (node (ref "U1") (pin "35") (pinfunction "PGEC1/AN1/RPB1/RB1_35") (pintype "bidirectional"))
    )
    (net (code "48") (name "/ICSP1_PGE_DATA") (class "Default")
      (node (ref "U1") (pin "36") (pinfunction "PGED1/AN0/RPB0/RB0_36") (pintype "bidirectional"))
    )
    (net (code "49") (name "/ICSP_MCLR") (class "Default")
      (node (ref "R21") (pin "1") (pinfunction "1_1") (pintype "passive"))
      (node (ref "U1") (pin "20") (pinfunction "~{MCLR}_20") (pintype "input"))
    )
    (net (code "51") (name "/PER_BTN0") (class "Default")
      (node (ref "U1") (pin "23") (pinfunction "AN25/RPE8/RE8_23") (pintype "bidirectional"))
    )
    (net (code "52") (name "/PER_BTN1") (class "Default")
      (node (ref "U1") (pin "24") (pinfunction "AN26/RPE9/RE9_24") (pintype "bidirectional"))
    )
    (net (code "54") (name "/PER_LED0") (class "Default")
      (node (ref "U1") (pin "26") (pinfunction "AN4/C1INB/RB4_26") (pintype "bidirectional"))
    )
    (net (code "55") (name "/PER_LED1") (class "Default")
      (node (ref "U1") (pin "25") (pinfunction "AN45/C1INA/RPB5/RB5_25") (pintype "bidirectional"))
    )
    (net (code "57") (name "/RESET") (class "Default")
      (node (ref "C1") (pin "1") (pinfunction "1_1") (pintype "passive"))
      (node (ref "Q1") (pin "1") (pinfunction "G_1") (pintype "passive"))
      (node (ref "R18") (pin "1") (pinfunction "1_1") (pintype "passive"))
    )
    (net (code "58") (name "/SPI1_MISO_0") (class "Default")
      (node (ref "R3") (pin "2") (pinfunction "2_2") (pintype "passive"))
      (node (ref "U1") (pin "48") (pinfunction "EBIA7/AN49/RPB9/PMA7/RB9_48") (pintype "bidirectional"))
    )
    (net (code "59") (name "/SPI1_MISO_1") (class "Default")
      (node (ref "R3") (pin "1") (pinfunction "1_1") (pintype "passive"))
    )
    (net (code "60") (name "/SPI1_MOSI_0") (class "Default")
      (node (ref "R2") (pin "2") (pinfunction "2_2") (pintype "passive"))
      (node (ref "U1") (pin "49") (pinfunction "CVREFOUT/AN5/RPB10/RB10_49") (pintype "bidirectional"))
    )
    (net (code "61") (name "/SPI1_MOSI_1") (class "Default")
      (node (ref "R2") (pin "1") (pinfunction "1_1") (pintype "passive"))
    )
    (net (code "62") (name "/SPI1_SCK_0") (class "Default")
      (node (ref "R1") (pin "2") (pinfunction "2_2") (pintype "passive"))
      (node (ref "U1") (pin "109") (pinfunction "RPD1/SCK1/RD1_109") (pintype "bidirectional"))
    )
    (net (code "63") (name "/SPI1_SCK_1") (class "Default")
      (node (ref "R1") (pin "1") (pinfunction "1_1") (pintype "passive"))
    )
    (net (code "64") (name "/UART1_RX_PIC") (class "Default")
      (node (ref "U1") (pin "90") (pinfunction "EBIA9/RPF4/SDA5/PMA9/RF4_90") (pintype "bidirectional+no_connect"))
    )
    (net (code "65") (name "/UART1_TX_PIC") (class "Default")
      (node (ref "U1") (pin "91") (pinfunction "EBIA8/RPF5/SCL5/PMA8/RF5_91") (pintype "bidirectional"))
    )
    (net (code "66") (name "/UART2_RX_PIC_0") (class "Default")
      (node (ref "R7") (pin "2") (pinfunction "2_2") (pintype "passive"))
      (node (ref "U1") (pin "118") (pinfunction "~{SQICS0}/RPD4/RD4_118") (pintype "bidirectional"))
    )
    (net (code "67") (name "/UART2_RX_PIC_1") (class "Default")
      (node (ref "R7") (pin "1") (pinfunction "1_1") (pintype "passive"))
    )
    (net (code "68") (name "/UART2_TX_PIC_0") (class "Default")
      (node (ref "R6") (pin "2") (pinfunction "2_2") (pintype "passive"))
      (node (ref "U1") (pin "119") (pinfunction "~{SQICS1}/RPD5/RD5_119") (pintype "bidirectional"))
    )
    (net (code "69") (name "/UART2_TX_PIC_1") (class "Default")
      (node (ref "R6") (pin "1") (pinfunction "1_1") (pintype "passive"))
    )
    (net (code "78") (name "GND") (class "Default")
      (node (ref "C1") (pin "2") (pinfunction "2_2") (pintype "passive"))
      (node (ref "C10") (pin "2") (pinfunction "2_2") (pintype "passive"))
      (node (ref "C11") (pin "2") (pinfunction "2_2") (pintype "passive"))
      (node (ref "C12") (pin "2") (pinfunction "2_2") (pintype "passive"))
      (node (ref "C13") (pin "1") (pinfunction "1_1") (pintype "passive"))
      (node (ref "C14") (pin "1") (pinfunction "1_1") (pintype "passive"))
      (node (ref "C15") (pin "1") (pinfunction "1_1") (pintype "passive"))
      (node (ref "C2") (pin "2") (pinfunction "2_2") (pintype "passive"))
      (node (ref "C3") (pin "2") (pinfunction "2_2") (pintype "passive"))
      (node (ref "C4") (pin "2") (pinfunction "2_2") (pintype "passive"))
      (node (ref "C5") (pin "2") (pinfunction "2_2") (pintype "passive"))
      (node (ref "C6") (pin "2") (pinfunction "2_2") (pintype "passive"))
      (node (ref "C7") (pin "2") (pinfunction "2_2") (pintype "passive"))
      (node (ref "C8") (pin "2") (pinfunction "2_2") (pintype "passive"))
      (node (ref "C9") (pin "2") (pinfunction "2_2") (pintype "passive"))
      (node (ref "Q1") (pin "2") (pinfunction "S_2") (pintype "passive"))
      (node (ref "R19") (pin "1") (pinfunction "1_1") (pintype "passive"))
      (node (ref "U1") (pin "108") (pinfunction "VSS_108") (pintype "power_in"))
      (node (ref "U1") (pin "123") (pinfunction "VSS_123") (pintype "power_in"))
      (node (ref "U1") (pin "136") (pinfunction "VSS_136") (pintype "power_in"))
      (node (ref "U1") (pin "17") (pinfunction "VSS_17") (pintype "power_in"))
      (node (ref "U1") (pin "32") (pinfunction "VSS_32") (pintype "power_in"))
      (node (ref "U1") (pin "42") (pinfunction "AVSS_42") (pintype "power_in"))
      (node (ref "U1") (pin "54") (pinfunction "VSS_54") (pintype "power_in"))
      (node (ref "U1") (pin "63") (pinfunction "VSS_63") (pintype "power_in"))
      (node (ref "U1") (pin "75") (pinfunction "VSS_75") (pintype "power_in"))
      (node (ref "U1") (pin "89") (pinfunction "VSS_89") (pintype "power_in"))
      (node (ref "Y1") (pin "2") (pinfunction "GND_2") (pintype "power_in"))
      (node (ref "Y2") (pin "2") (pinfunction "GND_2") (pintype "power_in"))
      (node (ref "Y3") (pin "2") (pinfunction "GND_2") (pintype "power_in"))
    )
    (net (code "79") (name "Net-(C2-Pad1)") (class "Default")
      (node (ref "C2") (pin "1") (pinfunction "1_1") (pintype "passive"))
      (node (ref "R20") (pin "1") (pinfunction "1_1") (pintype "passive"))
      (node (ref "R21") (pin "2") (pinfunction "2_2") (pintype "passive"))
      (node (ref "R22") (pin "1") (pinfunction "1_1") (pintype "passive"))
    )
    (net (code "80") (name "Net-(Q1-D)") (class "Default")
      (node (ref "Q1") (pin "3") (pinfunction "D_3") (pintype "passive"))
      (node (ref "R22") (pin "2") (pinfunction "2_2") (pintype "passive"))
    )
    (net (code "81") (name "Net-(R18-Pad2)") (class "Default")
      (node (ref "R18") (pin "2") (pinfunction "2_2") (pintype "passive"))
      (node (ref "R19") (pin "2") (pinfunction "2_2") (pintype "passive"))
      (node (ref "S1") (pin "2") (pinfunction "2_2") (pintype "passive"))
    )
    (net (code "82") (name "Net-(U1D-AVDD)") (class "Default")
      (node (ref "C3") (pin "1") (pinfunction "1_1") (pintype "passive"))
      (node (ref "FB1") (pin "2") (pinfunction "2_2") (pintype "passive"))
      (node (ref "U1") (pin "41") (pinfunction "AVDD_41") (pintype "power_in"))
    )
    (net (code "83") (name "unconnected-(S1-Pad1)") (class "Default")
      (node (ref "S1") (pin "1") (pinfunction "1_1") (pintype "passive+no_connect"))
    )
    (net (code "84") (name "unconnected-(S1-Pad3)") (class "Default")
      (node (ref "S1") (pin "3") (pinfunction "3_3") (pintype "passive+no_connect"))
    )
    (net (code "85") (name "unconnected-(U1A-AN2{slash}C2INB{slash}RPB2{slash}RB2-Pad34)") (class "Default")
      (node (ref "U1") (pin "34") (pinfunction "AN2/C2INB/RPB2/RB2_34") (pintype "bidirectional+no_connect"))
    )
    (net (code "86") (name "unconnected-(U1A-AN3{slash}C2INA{slash}RPB3{slash}RB3-Pad31)") (class "Default")
      (node (ref "U1") (pin "31") (pinfunction "AN3/C2INA/RPB3/RB3_31") (pintype "bidirectional+no_connect"))
    )
    (net (code "87") (name "unconnected-(U1A-AN6{slash}RB11-Pad50)") (class "Default")
      (node (ref "U1") (pin "50") (pinfunction "AN6/RB11_50") (pintype "bidirectional+no_connect"))
    )
    (net (code "88") (name "unconnected-(U1A-AN7{slash}RB12-Pad59)") (class "Default")
      (node (ref "U1") (pin "59") (pinfunction "AN7/RB12_59") (pintype "bidirectional+no_connect"))
    )
    (net (code "89") (name "unconnected-(U1A-AN8{slash}RB13-Pad60)") (class "Default")
      (node (ref "U1") (pin "60") (pinfunction "AN8/RB13_60") (pintype "bidirectional+no_connect"))
    )
    (net (code "90") (name "unconnected-(U1A-AN9{slash}RPB14{slash}SCK3{slash}RB14-Pad61)") (class "Default")
      (node (ref "U1") (pin "61") (pinfunction "AN9/RPB14/SCK3/RB14_61") (pintype "bidirectional+no_connect"))
    )
    (net (code "91") (name "unconnected-(U1A-AN10{slash}RPB15{slash}OCFB{slash}RB15-Pad62)") (class "Default")
      (node (ref "U1") (pin "62") (pinfunction "AN10/RPB15/OCFB/RB15_62") (pintype "bidirectional+no_connect"))
    )
    (net (code "92") (name "unconnected-(U1A-AN32{slash}RPD14{slash}RD14-Pad69)") (class "Default")
      (node (ref "U1") (pin "69") (pinfunction "AN32/RPD14/RD14_69") (pintype "bidirectional+no_connect"))
    )
    (net (code "93") (name "unconnected-(U1A-AN33{slash}RPD15{slash}SCK6{slash}RD15-Pad70)") (class "Default")
      (node (ref "U1") (pin "70") (pinfunction "AN33/RPD15/SCK6/RD15_70") (pintype "bidirectional+no_connect"))
    )
    (net (code "94") (name "unconnected-(U1A-EBIA5{slash}AN34{slash}PMA5{slash}RA5-Pad2)") (class "Default")
      (node (ref "U1") (pin "2") (pinfunction "EBIA5/AN34/PMA5/RA5_2") (pintype "bidirectional+no_connect"))
    )
    (net (code "95") (name "unconnected-(U1A-EBIA6{slash}AN22{slash}RPC1{slash}PMA6{slash}RC1-Pad6)") (class "Default")
      (node (ref "U1") (pin "6") (pinfunction "EBIA6/AN22/RPC1/PMA6/RC1_6") (pintype "bidirectional+no_connect"))
    )
    (net (code "96") (name "unconnected-(U1A-EBIA10{slash}AN48{slash}RPB8{slash}PMA10{slash}RB8-Pad47)") (class "Default")
      (node (ref "U1") (pin "47") (pinfunction "EBIA10/AN48/RPB8/PMA10/RB8_47") (pintype "bidirectional+no_connect"))
    )
    (net (code "97") (name "unconnected-(U1A-EBIA12{slash}AN21{slash}RPC2{slash}PMA12{slash}RC2-Pad11)") (class "Default")
      (node (ref "U1") (pin "11") (pinfunction "EBIA12/AN21/RPC2/PMA12/RC2_11") (pintype "bidirectional+no_connect"))
    )
    (net (code "98") (name "unconnected-(U1A-EBIA14{slash}PMCS1{slash}PMA14{slash}RA4-Pad87)") (class "Default")
      (node (ref "U1") (pin "87") (pinfunction "EBIA14/PMCS1/PMA14/RA4_87") (pintype "bidirectional+no_connect"))
    )
    (net (code "99") (name "unconnected-(U1A-EBIA15{slash}RPD9{slash}PMCS2{slash}PMA15{slash}RD9-Pad97)") (class "Default")
      (node (ref "U1") (pin "97") (pinfunction "EBIA15/RPD9/PMCS2/PMA15/RD9_97") (pintype "bidirectional+no_connect"))
    )
    (net (code "100") (name "unconnected-(U1A-EBID12{slash}RPD12{slash}PMD12{slash}RD12-Pad112)") (class "Default")
      (node (ref "U1") (pin "112") (pinfunction "EBID12/RPD12/PMD12/RD12_112") (pintype "bidirectional+no_connect"))
    )
    (net (code "101") (name "unconnected-(U1A-EBID13{slash}PMD13{slash}RD13-Pad113)") (class "Default")
      (node (ref "U1") (pin "113") (pinfunction "EBID13/PMD13/RD13_113") (pintype "bidirectional+no_connect"))
    )
    (net (code "102") (name "unconnected-(U1A-EBID14{slash}RPD2{slash}PMD14{slash}RD2-Pad110)") (class "Default")
      (node (ref "U1") (pin "110") (pinfunction "EBID14/RPD2/PMD14/RD2_110") (pintype "bidirectional+no_connect"))
    )
    (net (code "103") (name "unconnected-(U1A-EBID15{slash}RPD3{slash}PMD15{slash}RD3-Pad111)") (class "Default")
      (node (ref "U1") (pin "111") (pinfunction "EBID15/RPD3/PMD15/RD3_111") (pintype "bidirectional+no_connect"))
    )
    (net (code "104") (name "unconnected-(U1A-EBIRDY1{slash}SDA2{slash}RA3-Pad86)") (class "Default")
      (node (ref "U1") (pin "86") (pinfunction "EBIRDY1/SDA2/RA3_86") (pintype "bidirectional+no_connect"))
    )
    (net (code "105") (name "unconnected-(U1A-ETXCLK{slash}RPD7{slash}RD7-Pad121)") (class "Default")
      (node (ref "U1") (pin "121") (pinfunction "ETXCLK/RPD7/RD7_121") (pintype "bidirectional+no_connect"))
    )
    (net (code "106") (name "unconnected-(U1A-OSC2{slash}CLKO{slash}RC15-Pad72)") (class "Default")
      (node (ref "U1") (pin "72") (pinfunction "OSC2/CLKO/RC15_72") (pintype "bidirectional+no_connect"))
    )
    (net (code "107") (name "unconnected-(U1A-PGEC2{slash}AN46{slash}RPB6{slash}RB6-Pad37)") (class "Default")
      (node (ref "U1") (pin "37") (pinfunction "PGEC2/AN46/RPB6/RB6_37") (pintype "bidirectional+no_connect"))
    )
    (net (code "108") (name "unconnected-(U1A-PGED2{slash}AN47{slash}RPB7{slash}RB7-Pad38)") (class "Default")
      (node (ref "U1") (pin "38") (pinfunction "PGED2/AN47/RPB7/RB7_38") (pintype "bidirectional+no_connect"))
    )
    (net (code "109") (name "unconnected-(U1A-RPD0{slash}RTCC{slash}INT0{slash}RD0-Pad104)") (class "Default")
      (node (ref "U1") (pin "104") (pinfunction "RPD0/RTCC/INT0/RD0_104") (pintype "bidirectional+no_connect"))
    )
    (net (code "110") (name "unconnected-(U1A-RPD10{slash}SCK4{slash}RD10-Pad98)") (class "Default")
      (node (ref "U1") (pin "98") (pinfunction "RPD10/SCK4/RD10_98") (pintype "bidirectional+no_connect"))
    )
    (net (code "111") (name "unconnected-(U1A-SCL2{slash}RA2-Pad85)") (class "Default")
      (node (ref "U1") (pin "85") (pinfunction "SCL2/RA2_85") (pintype "bidirectional+no_connect"))
    )
    (net (code "112") (name "unconnected-(U1A-SOSCI{slash}RPC13{slash}RC13-Pad105)") (class "Default")
      (node (ref "U1") (pin "105") (pinfunction "SOSCI/RPC13/RC13_105") (pintype "bidirectional+no_connect"))
    )
    (net (code "113") (name "unconnected-(U1A-TCK{slash}AN29{slash}RA1-Pad56)") (class "Default")
      (node (ref "U1") (pin "56") (pinfunction "TCK/AN29/RA1_56") (pintype "bidirectional+no_connect"))
    )
    (net (code "114") (name "unconnected-(U1A-TMS{slash}AN24{slash}RA0-Pad22)") (class "Default")
      (node (ref "U1") (pin "22") (pinfunction "TMS/AN24/RA0_22") (pintype "bidirectional+no_connect"))
    )
    (net (code "115") (name "unconnected-(U1A-TRCLK{slash}SQICLK{slash}RA6-Pad129)") (class "Default")
      (node (ref "U1") (pin "129") (pinfunction "TRCLK/SQICLK/RA6_129") (pintype "bidirectional+no_connect"))
    )
    (net (code "116") (name "unconnected-(U1A-TRD3{slash}SQID3{slash}RA7-Pad130)") (class "Default")
      (node (ref "U1") (pin "130") (pinfunction "TRD3/SQID3/RA7_130") (pintype "bidirectional+no_connect"))
    )
    (net (code "117") (name "unconnected-(U1A-VREF+{slash}CVREF+{slash}AN28{slash}RA10-Pad40)") (class "Default")
      (node (ref "U1") (pin "40") (pinfunction "VREF+/CVREF+/AN28/RA10_40") (pintype "bidirectional+no_connect"))
    )
    (net (code "118") (name "unconnected-(U1A-VREF-{slash}CVREF-{slash}AN27{slash}RA9-Pad39)") (class "Default")
      (node (ref "U1") (pin "39") (pinfunction "VREF-/CVREF-/AN27/RA9_39") (pintype "bidirectional+no_connect"))
    )
    (net (code "119") (name "unconnected-(U1A-~{EBIOE}{slash}AN19{slash}RPC4{slash}PMRD{slash}RC4-Pad13)") (class "Default")
      (node (ref "U1") (pin "13") (pinfunction "~{EBIOE}/AN19/RPC4/PMRD/RC4_13") (pintype "bidirectional+no_connect"))
    )
    (net (code "120") (name "unconnected-(U1A-~{EBIWE}{slash}AN20{slash}RPC3{slash}PMWR{slash}RC3-Pad12)") (class "Default")
      (node (ref "U1") (pin "12") (pinfunction "~{EBIWE}/AN20/RPC3/PMWR/RC3_12") (pintype "bidirectional+no_connect"))
    )
    (net (code "121") (name "unconnected-(U1B-AN12{slash}C2IND{slash}RPG8{slash}SCL4{slash}RG8-Pad16)") (class "Default")
      (node (ref "U1") (pin "16") (pinfunction "AN12/C2IND/RPG8/SCL4/RG8_16") (pintype "bidirectional+no_connect"))
    )
    (net (code "122") (name "unconnected-(U1B-AN13{slash}C1INC{slash}RPG7{slash}SDA4{slash}RG7-Pad15)") (class "Default")
      (node (ref "U1") (pin "15") (pinfunction "AN13/C1INC/RPG7/SDA4/RG7_15") (pintype "bidirectional+no_connect"))
    )
    (net (code "123") (name "unconnected-(U1B-AN14{slash}C1IND{slash}RPG6{slash}SCK2{slash}RG6-Pad14)") (class "Default")
      (node (ref "U1") (pin "14") (pinfunction "AN14/C1IND/RPG6/SCK2/RG6_14") (pintype "bidirectional+no_connect"))
    )
    (net (code "124") (name "unconnected-(U1B-AN23{slash}RG15-Pad1)") (class "Default")
      (node (ref "U1") (pin "1") (pinfunction "AN23/RG15_1") (pintype "bidirectional+no_connect"))
    )
    (net (code "125") (name "unconnected-(U1B-AN38{slash}ETXD2{slash}RH0-Pad43)") (class "Default")
      (node (ref "U1") (pin "43") (pinfunction "AN38/ETXD2/RH0_43") (pintype "bidirectional+no_connect"))
    )
    (net (code "126") (name "unconnected-(U1B-AN39{slash}ETXD3{slash}RH1-Pad44)") (class "Default")
      (node (ref "U1") (pin "44") (pinfunction "AN39/ETXD3/RH1_44") (pintype "bidirectional+no_connect"))
    )
    (net (code "127") (name "unconnected-(U1B-AN42{slash}ERXD2{slash}RH6-Pad67)") (class "Default")
      (node (ref "U1") (pin "67") (pinfunction "AN42/ERXD2/RH6_67") (pintype "bidirectional+no_connect"))
    )
    (net (code "128") (name "unconnected-(U1B-EBIA2{slash}AN11{slash}C2INC{slash}RPG9{slash}PMA2{slash}RG9-Pad21)") (class "Default")
      (node (ref "U1") (pin "21") (pinfunction "EBIA2/AN11/C2INC/RPG9/PMA2/RG9_21") (pintype "bidirectional+no_connect"))
    )
    (net (code "129") (name "unconnected-(U1B-EBIA4{slash}PMA4{slash}RH7-Pad68)") (class "Default")
      (node (ref "U1") (pin "68") (pinfunction "EBIA4/PMA4/RH7_68") (pintype "bidirectional+no_connect"))
    )
    (net (code "130") (name "unconnected-(U1B-EBIA23{slash}RH15-Pad103)") (class "Default")
      (node (ref "U1") (pin "103") (pinfunction "EBIA23/RH15_103") (pintype "bidirectional+no_connect"))
    )
    (net (code "131") (name "unconnected-(U1B-EBID8{slash}RPG0{slash}PMD8{slash}RG0-Pad128)") (class "Default")
      (node (ref "U1") (pin "128") (pinfunction "EBID8/RPG0/PMD8/RG0_128") (pintype "bidirectional+no_connect"))
    )
    (net (code "132") (name "unconnected-(U1B-EBID9{slash}RPG1{slash}PMD9{slash}RG1-Pad127)") (class "Default")
      (node (ref "U1") (pin "127") (pinfunction "EBID9/RPG1/PMD9/RG1_127") (pintype "bidirectional+no_connect"))
    )
    (net (code "133") (name "unconnected-(U1B-EBID10{slash}RPF1{slash}PMD10{slash}RF1-Pad125)") (class "Default")
      (node (ref "U1") (pin "125") (pinfunction "EBID10/RPF1/PMD10/RF1_125") (pintype "bidirectional+no_connect"))
    )
    (net (code "134") (name "unconnected-(U1B-EBID11{slash}RPF0{slash}PMD11{slash}RF0-Pad124)") (class "Default")
      (node (ref "U1") (pin "124") (pinfunction "EBID11/RPF0/PMD11/RF0_124") (pintype "bidirectional+no_connect"))
    )
    (net (code "135") (name "unconnected-(U1B-EBIRDY2{slash}RH11-Pad84)") (class "Default")
      (node (ref "U1") (pin "84") (pinfunction "EBIRDY2/RH11_84") (pintype "bidirectional+no_connect"))
    )
    (net (code "136") (name "unconnected-(U1B-ECOL{slash}RH10-Pad83)") (class "Default")
      (node (ref "U1") (pin "83") (pinfunction "ECOL/RH10_83") (pintype "bidirectional+no_connect"))
    )
    (net (code "137") (name "unconnected-(U1B-ECRS{slash}RH12-Pad100)") (class "Default")
      (node (ref "U1") (pin "100") (pinfunction "ECRS/RH12_100") (pintype "bidirectional+no_connect"))
    )
    (net (code "138") (name "unconnected-(U1B-ERXD3{slash}RH9-Pad82)") (class "Default")
      (node (ref "U1") (pin "82") (pinfunction "ERXD3/RH9_82") (pintype "bidirectional+no_connect"))
    )
    (net (code "139") (name "unconnected-(U1B-RH3-Pad46)") (class "Default")
      (node (ref "U1") (pin "46") (pinfunction "RH3_46") (pintype "bidirectional+no_connect"))
    )
    (net (code "140") (name "unconnected-(U1B-RH14-Pad102)") (class "Default")
      (node (ref "U1") (pin "102") (pinfunction "RH14_102") (pintype "bidirectional+no_connect"))
    )
    (net (code "141") (name "unconnected-(U1B-RPF3{slash}USBID{slash}RF3-Pad78)") (class "Default")
      (node (ref "U1") (pin "78") (pinfunction "RPF3/USBID/RF3_78") (pintype "bidirectional+no_connect"))
    )
    (net (code "142") (name "unconnected-(U1B-SCL3{slash}RPF8{slash}RF8-Pad80)") (class "Default")
      (node (ref "U1") (pin "80") (pinfunction "SCL3/RPF8/RF8_80") (pintype "bidirectional+no_connect"))
    )
    (net (code "143") (name "unconnected-(U1B-SDA3{slash}RPF2{slash}RF2-Pad79)") (class "Default")
      (node (ref "U1") (pin "79") (pinfunction "SDA3/RPF2/RF2_79") (pintype "bidirectional+no_connect"))
    )
    (net (code "144") (name "unconnected-(U1B-TDI{slash}AN30{slash}RPF13{slash}SCK5{slash}RF13-Pad57)") (class "Default")
      (node (ref "U1") (pin "57") (pinfunction "TDI/AN30/RPF13/SCK5/RF13_57") (pintype "bidirectional+no_connect"))
    )
    (net (code "145") (name "unconnected-(U1B-TDO{slash}AN31{slash}RPF12{slash}RF12-Pad58)") (class "Default")
      (node (ref "U1") (pin "58") (pinfunction "TDO/AN31/RPF12/RF12_58") (pintype "bidirectional+no_connect"))
    )
    (net (code "146") (name "unconnected-(U1B-TRD0{slash}SQID0{slash}RG13-Pad141)") (class "Default")
      (node (ref "U1") (pin "141") (pinfunction "TRD0/SQID0/RG13_141") (pintype "bidirectional+no_connect"))
    )
    (net (code "147") (name "unconnected-(U1B-TRD1{slash}SQID1{slash}RG12-Pad140)") (class "Default")
      (node (ref "U1") (pin "140") (pinfunction "TRD1/SQID1/RG12_140") (pintype "bidirectional+no_connect"))
    )
    (net (code "148") (name "unconnected-(U1B-TRD2{slash}SQID2{slash}RG14-Pad139)") (class "Default")
      (node (ref "U1") (pin "139") (pinfunction "TRD2/SQID2/RG14_139") (pintype "bidirectional+no_connect"))
    )
    (net (code "149") (name "unconnected-(U1B-~{EBIRP}{slash}RH2-Pad45)") (class "Default")
      (node (ref "U1") (pin "45") (pinfunction "~{EBIRP}/RH2_45") (pintype "bidirectional+no_connect"))
    )
    (net (code "150") (name "unconnected-(U1C-D+-Pad77)") (class "Default")
      (node (ref "U1") (pin "77") (pinfunction "D+_77") (pintype "bidirectional+no_connect"))
    )
    (net (code "151") (name "unconnected-(U1C-D--Pad76)") (class "Default")
      (node (ref "U1") (pin "76") (pinfunction "D-_76") (pintype "bidirectional+no_connect"))
    )
    (net (code "152") (name "unconnected-(U1C-EBIA0{slash}PMA0{slash}RJ15-Pad30)") (class "Default")
      (node (ref "U1") (pin "30") (pinfunction "EBIA0/PMA0/RJ15_30") (pintype "bidirectional+no_connect"))
    )
    (net (code "153") (name "unconnected-(U1C-EBIA1{slash}PMA1{slash}RK1-Pad51)") (class "Default")
      (node (ref "U1") (pin "51") (pinfunction "EBIA1/PMA1/RK1_51") (pintype "bidirectional+no_connect"))
    )
    (net (code "154") (name "unconnected-(U1C-EBIA3{slash}PMA3{slash}RK2-Pad52)") (class "Default")
      (node (ref "U1") (pin "52") (pinfunction "EBIA3/PMA3/RK2_52") (pintype "bidirectional+no_connect"))
    )
    (net (code "155") (name "unconnected-(U1C-EBIA11{slash}PMA11{slash}RJ14-Pad29)") (class "Default")
      (node (ref "U1") (pin "29") (pinfunction "EBIA11/PMA11/RJ14_29") (pintype "bidirectional+no_connect"))
    )
    (net (code "156") (name "unconnected-(U1C-EBIA13{slash}PMA13{slash}RJ13-Pad28)") (class "Default")
      (node (ref "U1") (pin "28") (pinfunction "EBIA13/PMA13/RJ13_28") (pintype "bidirectional+no_connect"))
    )
    (net (code "157") (name "unconnected-(U1C-EBIA16{slash}RK0-Pad19)") (class "Default")
      (node (ref "U1") (pin "19") (pinfunction "EBIA16/RK0_19") (pintype "bidirectional+no_connect"))
    )
    (net (code "158") (name "unconnected-(U1C-EBIA17{slash}RK3-Pad53)") (class "Default")
      (node (ref "U1") (pin "53") (pinfunction "EBIA17/RK3_53") (pintype "bidirectional+no_connect"))
    )
    (net (code "159") (name "unconnected-(U1C-EBIA18{slash}RK4-Pad92)") (class "Default")
      (node (ref "U1") (pin "92") (pinfunction "EBIA18/RK4_92") (pintype "bidirectional+no_connect"))
    )
    (net (code "160") (name "unconnected-(U1C-EBIA19{slash}RK5-Pad93)") (class "Default")
      (node (ref "U1") (pin "93") (pinfunction "EBIA19/RK5_93") (pintype "bidirectional+no_connect"))
    )
    (net (code "161") (name "unconnected-(U1C-EBIA20{slash}RK6-Pad94)") (class "Default")
      (node (ref "U1") (pin "94") (pinfunction "EBIA20/RK6_94") (pintype "bidirectional+no_connect"))
    )
    (net (code "162") (name "unconnected-(U1C-EBIA21{slash}RK7-Pad126)") (class "Default")
      (node (ref "U1") (pin "126") (pinfunction "EBIA21/RK7_126") (pintype "bidirectional+no_connect"))
    )
    (net (code "163") (name "unconnected-(U1C-EBIA22{slash}RJ3-Pad117)") (class "Default")
      (node (ref "U1") (pin "117") (pinfunction "EBIA22/RJ3_117") (pintype "bidirectional+no_connect"))
    )
    (net (code "164") (name "unconnected-(U1C-EBIRDY3{slash}RJ2-Pad116)") (class "Default")
      (node (ref "U1") (pin "116") (pinfunction "EBIRDY3/RJ2_116") (pintype "bidirectional+no_connect"))
    )
    (net (code "165") (name "unconnected-(U1C-ETXERR{slash}RJ0-Pad114)") (class "Default")
      (node (ref "U1") (pin "114") (pinfunction "ETXERR/RJ0_114") (pintype "bidirectional+no_connect"))
    )
    (net (code "166") (name "unconnected-(U1C-~{EBIBS0}{slash}RJ12-Pad9)") (class "Default")
      (node (ref "U1") (pin "9") (pinfunction "~{EBIBS0}/RJ12_9") (pintype "bidirectional+no_connect"))
    )
    (net (code "167") (name "unconnected-(U1C-~{EBIBS1}{slash}RJ10-Pad10)") (class "Default")
      (node (ref "U1") (pin "10") (pinfunction "~{EBIBS1}/RJ10_10") (pintype "bidirectional+no_connect"))
    )
    (net (code "168") (name "unconnected-(U1C-~{EBICS0}{slash}RJ4-Pad131)") (class "Default")
      (node (ref "U1") (pin "131") (pinfunction "~{EBICS0}/RJ4_131") (pintype "bidirectional+no_connect"))
    )
    (net (code "169") (name "unconnected-(U1C-~{EBICS1}{slash}RJ5-Pad132)") (class "Default")
      (node (ref "U1") (pin "132") (pinfunction "~{EBICS1}/RJ5_132") (pintype "bidirectional+no_connect"))
    )
    (net (code "170") (name "unconnected-(U1C-~{EBICS2}{slash}RJ6-Pad133)") (class "Default")
      (node (ref "U1") (pin "133") (pinfunction "~{EBICS2}/RJ6_133") (pintype "bidirectional+no_connect"))
    )
    (net (code "171") (name "unconnected-(U1C-~{EBICS3}{slash}RJ7-Pad134)") (class "Default")
      (node (ref "U1") (pin "134") (pinfunction "~{EBICS3}/RJ7_134") (pintype "bidirectional+no_connect"))
    )
    (net (code "172") (name "unconnected-(U1D-VBUS-Pad73)") (class "Default")
      (node (ref "U1") (pin "73") (pinfunction "VBUS_73") (pintype "power_in+no_connect"))
    )
  )
)
